# EducaIno-EsquematicoV1_1.net
KiCad netlist of a schematic drawn in EAGLE
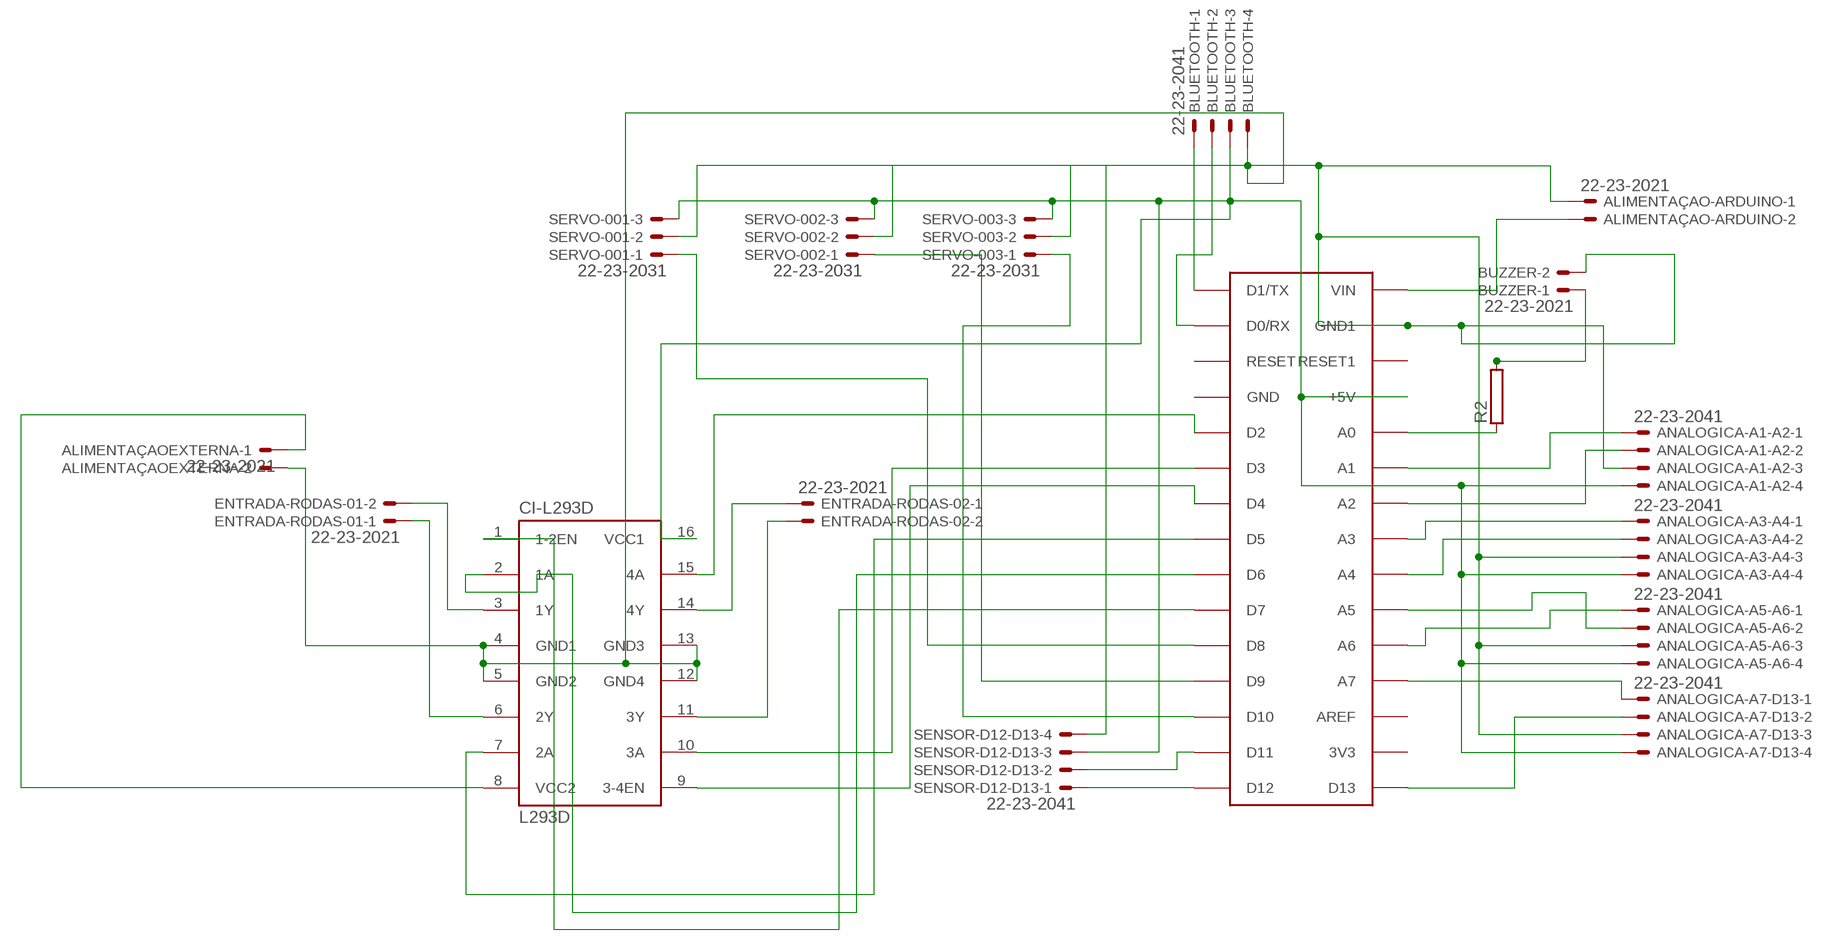
[diagram p0: schematic, sheet 1]

(export (version "E")
  (design (tool "Eeschema 10.0.6"))
  (components
    (comp (ref "ALIMENTAÇAO-ARDUINO")
      (value "22-23-2021")
      (footprint "eagle-import:22-23-2021")
      (fields (field (name "MF") "MOLEX"))
      (libsource (lib "eagle-import") (part "22-23-2021"))
    )
    (comp (ref "ALIMENTAÇAOEXTERNA")
      (value "22-23-2021")
      (footprint "eagle-import:22-23-2021")
      (fields (field (name "MF") "MOLEX"))
      (libsource (lib "eagle-import") (part "22-23-2021"))
    )
    (comp (ref "ANALOGICA-A1-A2")
      (value "22-23-2041")
      (footprint "eagle-import:22-23-2041")
      (fields (field (name "MF") "MOLEX"))
      (libsource (lib "eagle-import") (part "22-23-2041"))
    )
    (comp (ref "ANALOGICA-A3-A4")
      (value "22-23-2041")
      (footprint "eagle-import:22-23-2041")
      (fields (field (name "MF") "MOLEX"))
      (libsource (lib "eagle-import") (part "22-23-2041"))
    )
    (comp (ref "ANALOGICA-A5-A6")
      (value "22-23-2041")
      (footprint "eagle-import:22-23-2041")
      (fields (field (name "MF") "MOLEX"))
      (libsource (lib "eagle-import") (part "22-23-2041"))
    )
    (comp (ref "ANALOGICA-A7-D13")
      (value "22-23-2041")
      (footprint "eagle-import:22-23-2041")
      (fields (field (name "MF") "MOLEX"))
      (libsource (lib "eagle-import") (part "22-23-2041"))
    )
    (comp (ref "BLUETOOTH")
      (value "22-23-2041")
      (footprint "eagle-import:22-23-2041")
      (fields (field (name "MF") "MOLEX"))
      (libsource (lib "eagle-import") (part "22-23-2041"))
    )
    (comp (ref "BUZZER")
      (value "22-23-2021")
      (footprint "eagle-import:22-23-2021")
      (fields (field (name "MF") "MOLEX"))
      (libsource (lib "eagle-import") (part "22-23-2021"))
    )
    (comp (ref "CI-L293D")
      (value "L293D")
      (footprint "eagle-import:DIL16")
      (libsource (lib "eagle-import") (part "L293D"))
    )
    (comp (ref "ENTRADA-RODAS-01")
      (value "22-23-2021")
      (footprint "eagle-import:22-23-2021")
      (fields (field (name "MF") "MOLEX"))
      (libsource (lib "eagle-import") (part "22-23-2021"))
    )
    (comp (ref "ENTRADA-RODAS-02")
      (value "22-23-2021")
      (footprint "eagle-import:22-23-2021")
      (fields (field (name "MF") "MOLEX"))
      (libsource (lib "eagle-import") (part "22-23-2021"))
    )
    (comp (ref "R2")
      (value "RHPS58")
      (footprint "eagle-import:HPS58")
      (libsource (lib "eagle-import") (part "RHPS58"))
    )
    (comp (ref "SENSOR-D12-D13")
      (value "22-23-2041")
      (footprint "eagle-import:22-23-2041")
      (fields (field (name "MF") "MOLEX"))
      (libsource (lib "eagle-import") (part "22-23-2041"))
    )
    (comp (ref "SERVO-001")
      (value "22-23-2031")
      (footprint "eagle-import:22-23-2031")
      (fields (field (name "MF") "MOLEX"))
      (libsource (lib "eagle-import") (part "22-23-2031"))
    )
    (comp (ref "SERVO-002")
      (value "22-23-2031")
      (footprint "eagle-import:22-23-2031")
      (fields (field (name "MF") "MOLEX"))
      (libsource (lib "eagle-import") (part "22-23-2031"))
    )
    (comp (ref "SERVO-003")
      (value "22-23-2031")
      (footprint "eagle-import:22-23-2031")
      (fields (field (name "MF") "MOLEX"))
      (libsource (lib "eagle-import") (part "22-23-2031"))
    )
    (comp (ref "U$1")
      (value "ARDUINONANO")
      (footprint "eagle-import:PDIP-32")
      (libsource (lib "eagle-import") (part "ARDUINONANO"))
    )
  )
  (nets
    (net (code "1") (name "Net-(ALIMENTAÇAO-ARDUINOA-S)") (class "Default")
      (node (ref "ALIMENTAÇAO-ARDUINO") (pin "1") (pinfunction "S_1") (pintype "passive"))
      (node (ref "ALIMENTAÇAOEXTERNA") (pin "2") (pinfunction "S_2") (pintype "passive"))
      (node (ref "ANALOGICA-A1-A2") (pin "3") (pinfunction "S_3") (pintype "passive"))
      (node (ref "ANALOGICA-A3-A4") (pin "3") (pinfunction "S_3") (pintype "passive"))
      (node (ref "ANALOGICA-A5-A6") (pin "3") (pinfunction "S_3") (pintype "passive"))
      (node (ref "ANALOGICA-A7-D13") (pin "3") (pinfunction "S_3") (pintype "passive"))
      (node (ref "BLUETOOTH") (pin "4") (pinfunction "S_4") (pintype "passive"))
      (node (ref "BUZZER") (pin "2") (pinfunction "S_2") (pintype "passive"))
      (node (ref "CI-L293D") (pin "12") (pinfunction "GND4_12") (pintype "power_in"))
      (node (ref "CI-L293D") (pin "13") (pinfunction "GND3_13") (pintype "power_in"))
      (node (ref "CI-L293D") (pin "4") (pinfunction "GND1_4") (pintype "power_in"))
      (node (ref "CI-L293D") (pin "5") (pinfunction "GND2_5") (pintype "power_in"))
      (node (ref "SENSOR-D12-D13") (pin "4") (pinfunction "S_4") (pintype "passive"))
      (node (ref "SERVO-001") (pin "2") (pinfunction "S_2") (pintype "passive"))
      (node (ref "SERVO-002") (pin "2") (pinfunction "S_2") (pintype "passive"))
      (node (ref "SERVO-003") (pin "2") (pinfunction "S_2") (pintype "passive"))
      (node (ref "U$1") (pin "GND1") (pinfunction "GND1_GND1") (pintype "bidirectional"))
    )
    (net (code "2") (name "Net-(ALIMENTAÇAO-ARDUINOB-S)") (class "Default")
      (node (ref "ALIMENTAÇAO-ARDUINO") (pin "2") (pinfunction "S_2") (pintype "passive"))
      (node (ref "U$1") (pin "VIN") (pinfunction "VIN_VIN") (pintype "bidirectional"))
    )
    (net (code "3") (name "Net-(ALIMENTAÇAOEXTERNAA-S)") (class "Default")
      (node (ref "ALIMENTAÇAOEXTERNA") (pin "1") (pinfunction "S_1") (pintype "passive"))
      (node (ref "CI-L293D") (pin "8") (pinfunction "VCC2_8") (pintype "power_in"))
    )
    (net (code "4") (name "Net-(ANALOGICA-A1-A2A-S)") (class "Default")
      (node (ref "ANALOGICA-A1-A2") (pin "1") (pinfunction "S_1") (pintype "passive"))
      (node (ref "U$1") (pin "A1") (pinfunction "A1_A1") (pintype "bidirectional"))
    )
    (net (code "5") (name "Net-(ANALOGICA-A1-A2B-S)") (class "Default")
      (node (ref "ANALOGICA-A1-A2") (pin "2") (pinfunction "S_2") (pintype "passive"))
      (node (ref "U$1") (pin "A2") (pinfunction "A2_A2") (pintype "bidirectional"))
    )
    (net (code "6") (name "Net-(ANALOGICA-A1-A2D-S)") (class "Default")
      (node (ref "ANALOGICA-A1-A2") (pin "4") (pinfunction "S_4") (pintype "passive"))
      (node (ref "ANALOGICA-A3-A4") (pin "4") (pinfunction "S_4") (pintype "passive"))
      (node (ref "ANALOGICA-A5-A6") (pin "4") (pinfunction "S_4") (pintype "passive"))
      (node (ref "ANALOGICA-A7-D13") (pin "4") (pinfunction "S_4") (pintype "passive"))
      (node (ref "BLUETOOTH") (pin "3") (pinfunction "S_3") (pintype "passive"))
      (node (ref "CI-L293D") (pin "16") (pinfunction "VCC1_16") (pintype "power_in"))
      (node (ref "SENSOR-D12-D13") (pin "3") (pinfunction "S_3") (pintype "passive"))
      (node (ref "SERVO-001") (pin "3") (pinfunction "S_3") (pintype "passive"))
      (node (ref "SERVO-002") (pin "3") (pinfunction "S_3") (pintype "passive"))
      (node (ref "SERVO-003") (pin "3") (pinfunction "S_3") (pintype "passive"))
      (node (ref "U$1") (pin "+5V") (pinfunction "+5V_+5V") (pintype "bidirectional"))
    )
    (net (code "7") (name "Net-(ANALOGICA-A3-A4A-S)") (class "Default")
      (node (ref "ANALOGICA-A3-A4") (pin "1") (pinfunction "S_1") (pintype "passive"))
      (node (ref "U$1") (pin "A3") (pinfunction "A3_A3") (pintype "bidirectional"))
    )
    (net (code "8") (name "Net-(ANALOGICA-A3-A4B-S)") (class "Default")
      (node (ref "ANALOGICA-A3-A4") (pin "2") (pinfunction "S_2") (pintype "passive"))
      (node (ref "U$1") (pin "A4") (pinfunction "A4_A4") (pintype "bidirectional"))
    )
    (net (code "9") (name "Net-(ANALOGICA-A5-A6A-S)") (class "Default")
      (node (ref "ANALOGICA-A5-A6") (pin "1") (pinfunction "S_1") (pintype "passive"))
      (node (ref "U$1") (pin "A6") (pinfunction "A6_A6") (pintype "bidirectional"))
    )
    (net (code "10") (name "Net-(ANALOGICA-A5-A6B-S)") (class "Default")
      (node (ref "ANALOGICA-A5-A6") (pin "2") (pinfunction "S_2") (pintype "passive"))
      (node (ref "U$1") (pin "A5") (pinfunction "A5_A5") (pintype "bidirectional"))
    )
    (net (code "11") (name "Net-(ANALOGICA-A7-D13A-S)") (class "Default")
      (node (ref "ANALOGICA-A7-D13") (pin "1") (pinfunction "S_1") (pintype "passive"))
      (node (ref "U$1") (pin "A7") (pinfunction "A7_A7") (pintype "bidirectional"))
    )
    (net (code "12") (name "Net-(ANALOGICA-A7-D13B-S)") (class "Default")
      (node (ref "ANALOGICA-A7-D13") (pin "2") (pinfunction "S_2") (pintype "passive"))
      (node (ref "U$1") (pin "D13") (pinfunction "D13_D13") (pintype "bidirectional"))
    )
    (net (code "13") (name "Net-(BLUETOOTHA-S)") (class "Default")
      (node (ref "BLUETOOTH") (pin "1") (pinfunction "S_1") (pintype "passive"))
      (node (ref "U$1") (pin "D1/TX") (pinfunction "D1/TX_D1/TX") (pintype "bidirectional"))
    )
    (net (code "14") (name "Net-(BLUETOOTHB-S)") (class "Default")
      (node (ref "BLUETOOTH") (pin "2") (pinfunction "S_2") (pintype "passive"))
      (node (ref "U$1") (pin "D0/RX") (pinfunction "D0/RX_D0/RX") (pintype "bidirectional"))
    )
    (net (code "15") (name "Net-(BUZZERA-S)") (class "Default")
      (node (ref "BUZZER") (pin "1") (pinfunction "S_1") (pintype "passive"))
      (node (ref "R2") (pin "2") (pinfunction "2_2") (pintype "passive"))
    )
    (net (code "16") (name "Net-(CI-L293D-1-2EN)") (class "Default")
      (node (ref "CI-L293D") (pin "1") (pinfunction "1-2EN_1") (pintype "input"))
      (node (ref "U$1") (pin "D7") (pinfunction "D7_D7") (pintype "bidirectional"))
    )
    (net (code "17") (name "Net-(CI-L293D-1A)") (class "Default")
      (node (ref "CI-L293D") (pin "2") (pinfunction "1A_2") (pintype "input"))
      (node (ref "U$1") (pin "D6") (pinfunction "D6_D6") (pintype "bidirectional"))
    )
    (net (code "18") (name "Net-(CI-L293D-1Y)") (class "Default")
      (node (ref "CI-L293D") (pin "3") (pinfunction "1Y_3") (pintype "output"))
      (node (ref "ENTRADA-RODAS-01") (pin "2") (pinfunction "S_2") (pintype "passive"))
    )
    (net (code "19") (name "Net-(CI-L293D-2A)") (class "Default")
      (node (ref "CI-L293D") (pin "7") (pinfunction "2A_7") (pintype "input"))
      (node (ref "U$1") (pin "D5") (pinfunction "D5_D5") (pintype "bidirectional"))
    )
    (net (code "20") (name "Net-(CI-L293D-2Y)") (class "Default")
      (node (ref "CI-L293D") (pin "6") (pinfunction "2Y_6") (pintype "output"))
      (node (ref "ENTRADA-RODAS-01") (pin "1") (pinfunction "S_1") (pintype "passive"))
    )
    (net (code "21") (name "Net-(CI-L293D-3-4EN)") (class "Default")
      (node (ref "CI-L293D") (pin "9") (pinfunction "3-4EN_9") (pintype "input"))
      (node (ref "U$1") (pin "D4") (pinfunction "D4_D4") (pintype "bidirectional"))
    )
    (net (code "22") (name "Net-(CI-L293D-3A)") (class "Default")
      (node (ref "CI-L293D") (pin "10") (pinfunction "3A_10") (pintype "input"))
      (node (ref "U$1") (pin "D3") (pinfunction "D3_D3") (pintype "bidirectional"))
    )
    (net (code "23") (name "Net-(CI-L293D-3Y)") (class "Default")
      (node (ref "CI-L293D") (pin "11") (pinfunction "3Y_11") (pintype "output"))
      (node (ref "ENTRADA-RODAS-02") (pin "2") (pinfunction "S_2") (pintype "passive"))
    )
    (net (code "24") (name "Net-(CI-L293D-4A)") (class "Default")
      (node (ref "CI-L293D") (pin "15") (pinfunction "4A_15") (pintype "input"))
      (node (ref "U$1") (pin "D2") (pinfunction "D2_D2") (pintype "bidirectional"))
    )
    (net (code "25") (name "Net-(CI-L293D-4Y)") (class "Default")
      (node (ref "CI-L293D") (pin "14") (pinfunction "4Y_14") (pintype "output"))
      (node (ref "ENTRADA-RODAS-02") (pin "1") (pinfunction "S_1") (pintype "passive"))
    )
    (net (code "26") (name "Net-(R2-Pad1)") (class "Default")
      (node (ref "R2") (pin "1") (pinfunction "1_1") (pintype "passive"))
      (node (ref "U$1") (pin "A0") (pinfunction "A0_A0") (pintype "bidirectional"))
    )
    (net (code "27") (name "Net-(SENSOR-D12-D13A-S)") (class "Default")
      (node (ref "SENSOR-D12-D13") (pin "1") (pinfunction "S_1") (pintype "passive"))
      (node (ref "U$1") (pin "D12") (pinfunction "D12_D12") (pintype "bidirectional"))
    )
    (net (code "28") (name "Net-(SENSOR-D12-D13B-S)") (class "Default")
      (node (ref "SENSOR-D12-D13") (pin "2") (pinfunction "S_2") (pintype "passive"))
      (node (ref "U$1") (pin "D11") (pinfunction "D11_D11") (pintype "bidirectional"))
    )
    (net (code "29") (name "Net-(SERVO-001A-S)") (class "Default")
      (node (ref "SERVO-001") (pin "1") (pinfunction "S_1") (pintype "passive"))
      (node (ref "U$1") (pin "D8") (pinfunction "D8_D8") (pintype "bidirectional"))
    )
    (net (code "30") (name "Net-(SERVO-002A-S)") (class "Default")
      (node (ref "SERVO-002") (pin "1") (pinfunction "S_1") (pintype "passive"))
      (node (ref "U$1") (pin "D9") (pinfunction "D9_D9") (pintype "bidirectional"))
    )
    (net (code "31") (name "Net-(SERVO-003A-S)") (class "Default")
      (node (ref "SERVO-003") (pin "1") (pinfunction "S_1") (pintype "passive"))
      (node (ref "U$1") (pin "D10") (pinfunction "D10_D10") (pintype "bidirectional"))
    )
    (net (code "32") (name "unconnected-(U$1-Pad3V3)") (class "Default")
      (node (ref "U$1") (pin "3V3") (pinfunction "3V3_3V3") (pintype "bidirectional"))
    )
    (net (code "33") (name "unconnected-(U$1-PadAREF)") (class "Default")
      (node (ref "U$1") (pin "AREF") (pinfunction "AREF_AREF") (pintype "bidirectional"))
    )
    (net (code "34") (name "unconnected-(U$1-PadGND)") (class "Default")
      (node (ref "U$1") (pin "GND") (pinfunction "GND_GND") (pintype "bidirectional"))
    )
    (net (code "35") (name "unconnected-(U$1-PadRESET)") (class "Default")
      (node (ref "U$1") (pin "RESET") (pinfunction "RESET_RESET") (pintype "bidirectional"))
    )
    (net (code "36") (name "unconnected-(U$1-PadRESET1)") (class "Default")
      (node (ref "U$1") (pin "RESET1") (pinfunction "RESET1_RESET1") (pintype "bidirectional"))
    )
  )
)
